# gydrodrive_can.net
KiCad netlist of a schematic drawn in Altium Designer
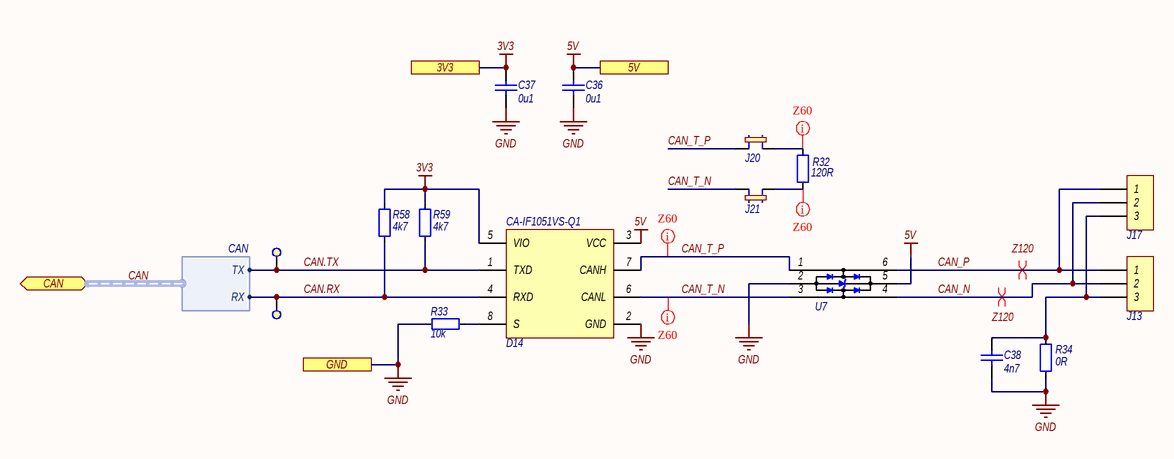
[diagram p0: gydrodrive_can.SchDoc]

(export (version "E")
  (design (tool "Eeschema 10.0.6"))
  (components
    (comp (ref "C36")
      (value "CAP_0805")
      (footprint "CAPC2012-0805M")
      (description "Конденсатор керамический, корпус 0805")
      (fields
        (field (name "CAPACITANCE") "0u1")
        (field (name "PART NUMBER") "CAPC_0805")
        (field (name "VOLTAGE") "50V")
      )
      (libsource (lib "StdLib") (part "CAP"))
    )
    (comp (ref "C37")
      (value "CAP_0805")
      (footprint "CAPC2012-0805M")
      (description "Конденсатор керамический, корпус 0805")
      (fields
        (field (name "CAPACITANCE") "0u1")
        (field (name "PART NUMBER") "CAPC_0805")
        (field (name "VOLTAGE") "50V")
      )
      (libsource (lib "StdLib") (part "CAP"))
    )
    (comp (ref "C38")
      (value "CAP_1206")
      (footprint "CAPC3216-1206M")
      (description "Конденсатор керамический, корпус 1206")
      (fields
        (field (name "CAPACITANCE") "4n7")
        (field (name "PART NUMBER") "CAPC_1206")
        (field (name "VOLTAGE") "50V")
      )
      (libsource (lib "StdLib") (part "CAP"))
    )
    (comp (ref "D14")
      (value "CA-IF1051VS-Q1")
      (footprint "SO8_N")
      (description "CAN интерфейс")
      (libsource (lib "StdLib") (part "CA-IF1051VS-Q1"))
    )
    (comp (ref "J13")
      (value "DG142V-5.08-03P")
      (footprint "DG142V-5.08-03P")
      (description "Клеммник 3-контактный, шаг 5.08 мм")
      (libsource (lib "StdLib") (part "PIN1x3"))
    )
    (comp (ref "J17")
      (value "DG142V-5.08-03P")
      (footprint "DG142V-5.08-03P")
      (description "Клеммник 3-контактный, шаг 5.08 мм")
      (libsource (lib "StdLib") (part "PIN1x3"))
    )
    (comp (ref "J20")
      (value "PLS-2.54-2 JUMP")
      (footprint "PLS-2-2.54")
      (description "Разъем штыревой шаг 2.54 мм")
      (libsource (lib "") (part "PIN1x2_JUMP_1"))
    )
    (comp (ref "J21")
      (value "PLS-2.54-2 JUMP")
      (footprint "PLS-2-2.54")
      (description "Разъем штыревой шаг 2.54 мм")
      (libsource (lib "StdLib") (part "PIN1x2_JUMP"))
    )
    (comp (ref "R32")
      (value "RES_1206")
      (footprint "RESC3216-1206M")
      (description "Рез-р, корпус 1206")
      (fields
        (field (name "RESISTANCE") "120R")
        (field (name "PART NUMBER") "RESC_1206")
        (field (name "TOLERANCE") "5%")
      )
      (libsource (lib "") (part "RES_1"))
    )
    (comp (ref "R33")
      (value "RES_0805")
      (footprint "RESC2012-0805M")
      (description "Рез-р, корпус 0805")
      (fields
        (field (name "RESISTANCE") "10k")
        (field (name "PART NUMBER") "RESC_0805")
        (field (name "TOLERANCE") "5%")
      )
      (libsource (lib "StdLib") (part "RES"))
    )
    (comp (ref "R34")
      (value "RES_1206")
      (footprint "RESC3216-1206M")
      (description "Рез-р, корпус 1206")
      (fields
        (field (name "RESISTANCE") "0R")
        (field (name "PART NUMBER") "RESC_1206")
        (field (name "TOLERANCE") "5%")
      )
      (libsource (lib "") (part "RES_2"))
    )
    (comp (ref "R58")
      (value "RES_0805")
      (footprint "RESC2012-0805M")
      (description "Рез-р, корпус 0805")
      (fields
        (field (name "RESISTANCE") "4k7")
        (field (name "PART NUMBER") "RESC_0805")
        (field (name "TOLERANCE") "5%")
      )
      (libsource (lib "") (part "RES_1"))
    )
    (comp (ref "R59")
      (value "RES_0805")
      (footprint "RESC2012-0805M")
      (description "Рез-р, корпус 0805")
      (fields
        (field (name "RESISTANCE") "4k7")
        (field (name "PART NUMBER") "RESC_0805")
        (field (name "TOLERANCE") "5%")
      )
      (libsource (lib "") (part "RES_1"))
    )
    (comp (ref "TP14")
      (value "Test point 1")
      (footprint "TP_1")
      (description "Тестовый контакт круглый 1 мм")
      (libsource (lib "StdLib") (part "Test point"))
    )
    (comp (ref "TP15")
      (value "Test point 1")
      (footprint "TP_1")
      (description "Тестовый контакт круглый 1 мм")
      (libsource (lib "StdLib") (part "Test point"))
    )
    (comp (ref "U7")
      (value "USBLC6-2SC6")
      (footprint "SOT23-6AM")
      (description "Диодная сборка для защиты дифференциальной линии")
      (fields (field (name "VOLTAGE") "5.25V"))
      (libsource (lib "StdLib") (part "USBLC6-2SC6"))
    )
  )
  (nets
    (net (code "2") (name "/CAN.RX") (class "Default")
      (node (ref "D14") (pin "4") (pinfunction "RXD_4") (pintype "passive"))
      (node (ref "R58") (pin "1") (pinfunction "1_1") (pintype "passive"))
      (node (ref "TP15") (pin "1") (pinfunction "1_1") (pintype "passive"))
    )
    (net (code "3") (name "/CAN.TX") (class "Default")
      (node (ref "D14") (pin "1") (pinfunction "TXD_1") (pintype "passive"))
      (node (ref "R59") (pin "1") (pinfunction "1_1") (pintype "passive"))
      (node (ref "TP14") (pin "1") (pinfunction "1_1") (pintype "passive"))
    )
    (net (code "4") (name "/CAN_N") (class "Default")
      (node (ref "J13") (pin "2") (pinfunction "2_2") (pintype "passive"))
      (node (ref "J17") (pin "2") (pinfunction "2_2") (pintype "passive"))
      (node (ref "U7") (pin "4") (pinfunction "IO2_4") (pintype "passive"))
    )
    (net (code "5") (name "/CAN_P") (class "Default")
      (node (ref "J13") (pin "1") (pinfunction "1_1") (pintype "passive"))
      (node (ref "J17") (pin "1") (pinfunction "1_1") (pintype "passive"))
      (node (ref "U7") (pin "6") (pinfunction "IO1_6") (pintype "passive"))
    )
    (net (code "6") (name "/CAN_T_N") (class "Default")
      (node (ref "D14") (pin "6") (pinfunction "CANL_6") (pintype "passive"))
      (node (ref "J21") (pin "2") (pinfunction "2_2") (pintype "passive"))
      (node (ref "U7") (pin "3") (pinfunction "IO2_3") (pintype "passive"))
    )
    (net (code "7") (name "/CAN_T_P") (class "Default")
      (node (ref "D14") (pin "7") (pinfunction "CANH_7") (pintype "passive"))
      (node (ref "J20") (pin "2") (pinfunction "2_2") (pintype "passive"))
      (node (ref "U7") (pin "1") (pinfunction "IO1_1") (pintype "passive"))
    )
    (net (code "9") (name "3V3") (class "Default")
      (node (ref "C37") (pin "2") (pinfunction "2_2") (pintype "passive"))
      (node (ref "D14") (pin "5") (pinfunction "VIO_5") (pintype "passive"))
      (node (ref "R58") (pin "2") (pinfunction "2_2") (pintype "passive"))
      (node (ref "R59") (pin "2") (pinfunction "2_2") (pintype "passive"))
    )
    (net (code "10") (name "5V") (class "Default")
      (node (ref "C36") (pin "2") (pinfunction "2_2") (pintype "passive"))
      (node (ref "D14") (pin "3") (pinfunction "VCC_3") (pintype "passive"))
      (node (ref "U7") (pin "5") (pinfunction "Vbus_5") (pintype "passive"))
    )
    (net (code "11") (name "GND") (class "Default")
      (node (ref "C36") (pin "1") (pinfunction "1_1") (pintype "passive"))
      (node (ref "C37") (pin "1") (pinfunction "1_1") (pintype "passive"))
      (node (ref "C38") (pin "1") (pinfunction "1_1") (pintype "passive"))
      (node (ref "D14") (pin "2") (pinfunction "GND_2") (pintype "passive"))
      (node (ref "R33") (pin "1") (pinfunction "1_1") (pintype "passive"))
      (node (ref "R34") (pin "2") (pinfunction "2_2") (pintype "passive"))
      (node (ref "U7") (pin "2") (pinfunction "GND_2") (pintype "passive"))
    )
    (net (code "12") (name "Net-(C38-Pad2)") (class "Default")
      (node (ref "C38") (pin "2") (pinfunction "2_2") (pintype "passive"))
      (node (ref "J13") (pin "3") (pinfunction "3_3") (pintype "passive"))
      (node (ref "J17") (pin "3") (pinfunction "3_3") (pintype "passive"))
      (node (ref "R34") (pin "1") (pinfunction "1_1") (pintype "passive"))
    )
    (net (code "13") (name "Net-(D14-S)") (class "Default")
      (node (ref "D14") (pin "8") (pinfunction "S_8") (pintype "passive"))
      (node (ref "R33") (pin "2") (pinfunction "2_2") (pintype "passive"))
    )
    (net (code "14") (name "Net-(J20-Pad1)") (class "Default")
      (node (ref "J20") (pin "1") (pinfunction "1_1") (pintype "passive"))
      (node (ref "R32") (pin "2") (pinfunction "2_2") (pintype "passive"))
    )
    (net (code "15") (name "Net-(J21-Pad1)") (class "Default")
      (node (ref "J21") (pin "1") (pinfunction "1_1") (pintype "passive"))
      (node (ref "R32") (pin "1") (pinfunction "1_1") (pintype "passive"))
    )
  )
)
